# RPi_Extension_load.net
KiCad netlist of a schematic drawn in EAGLE
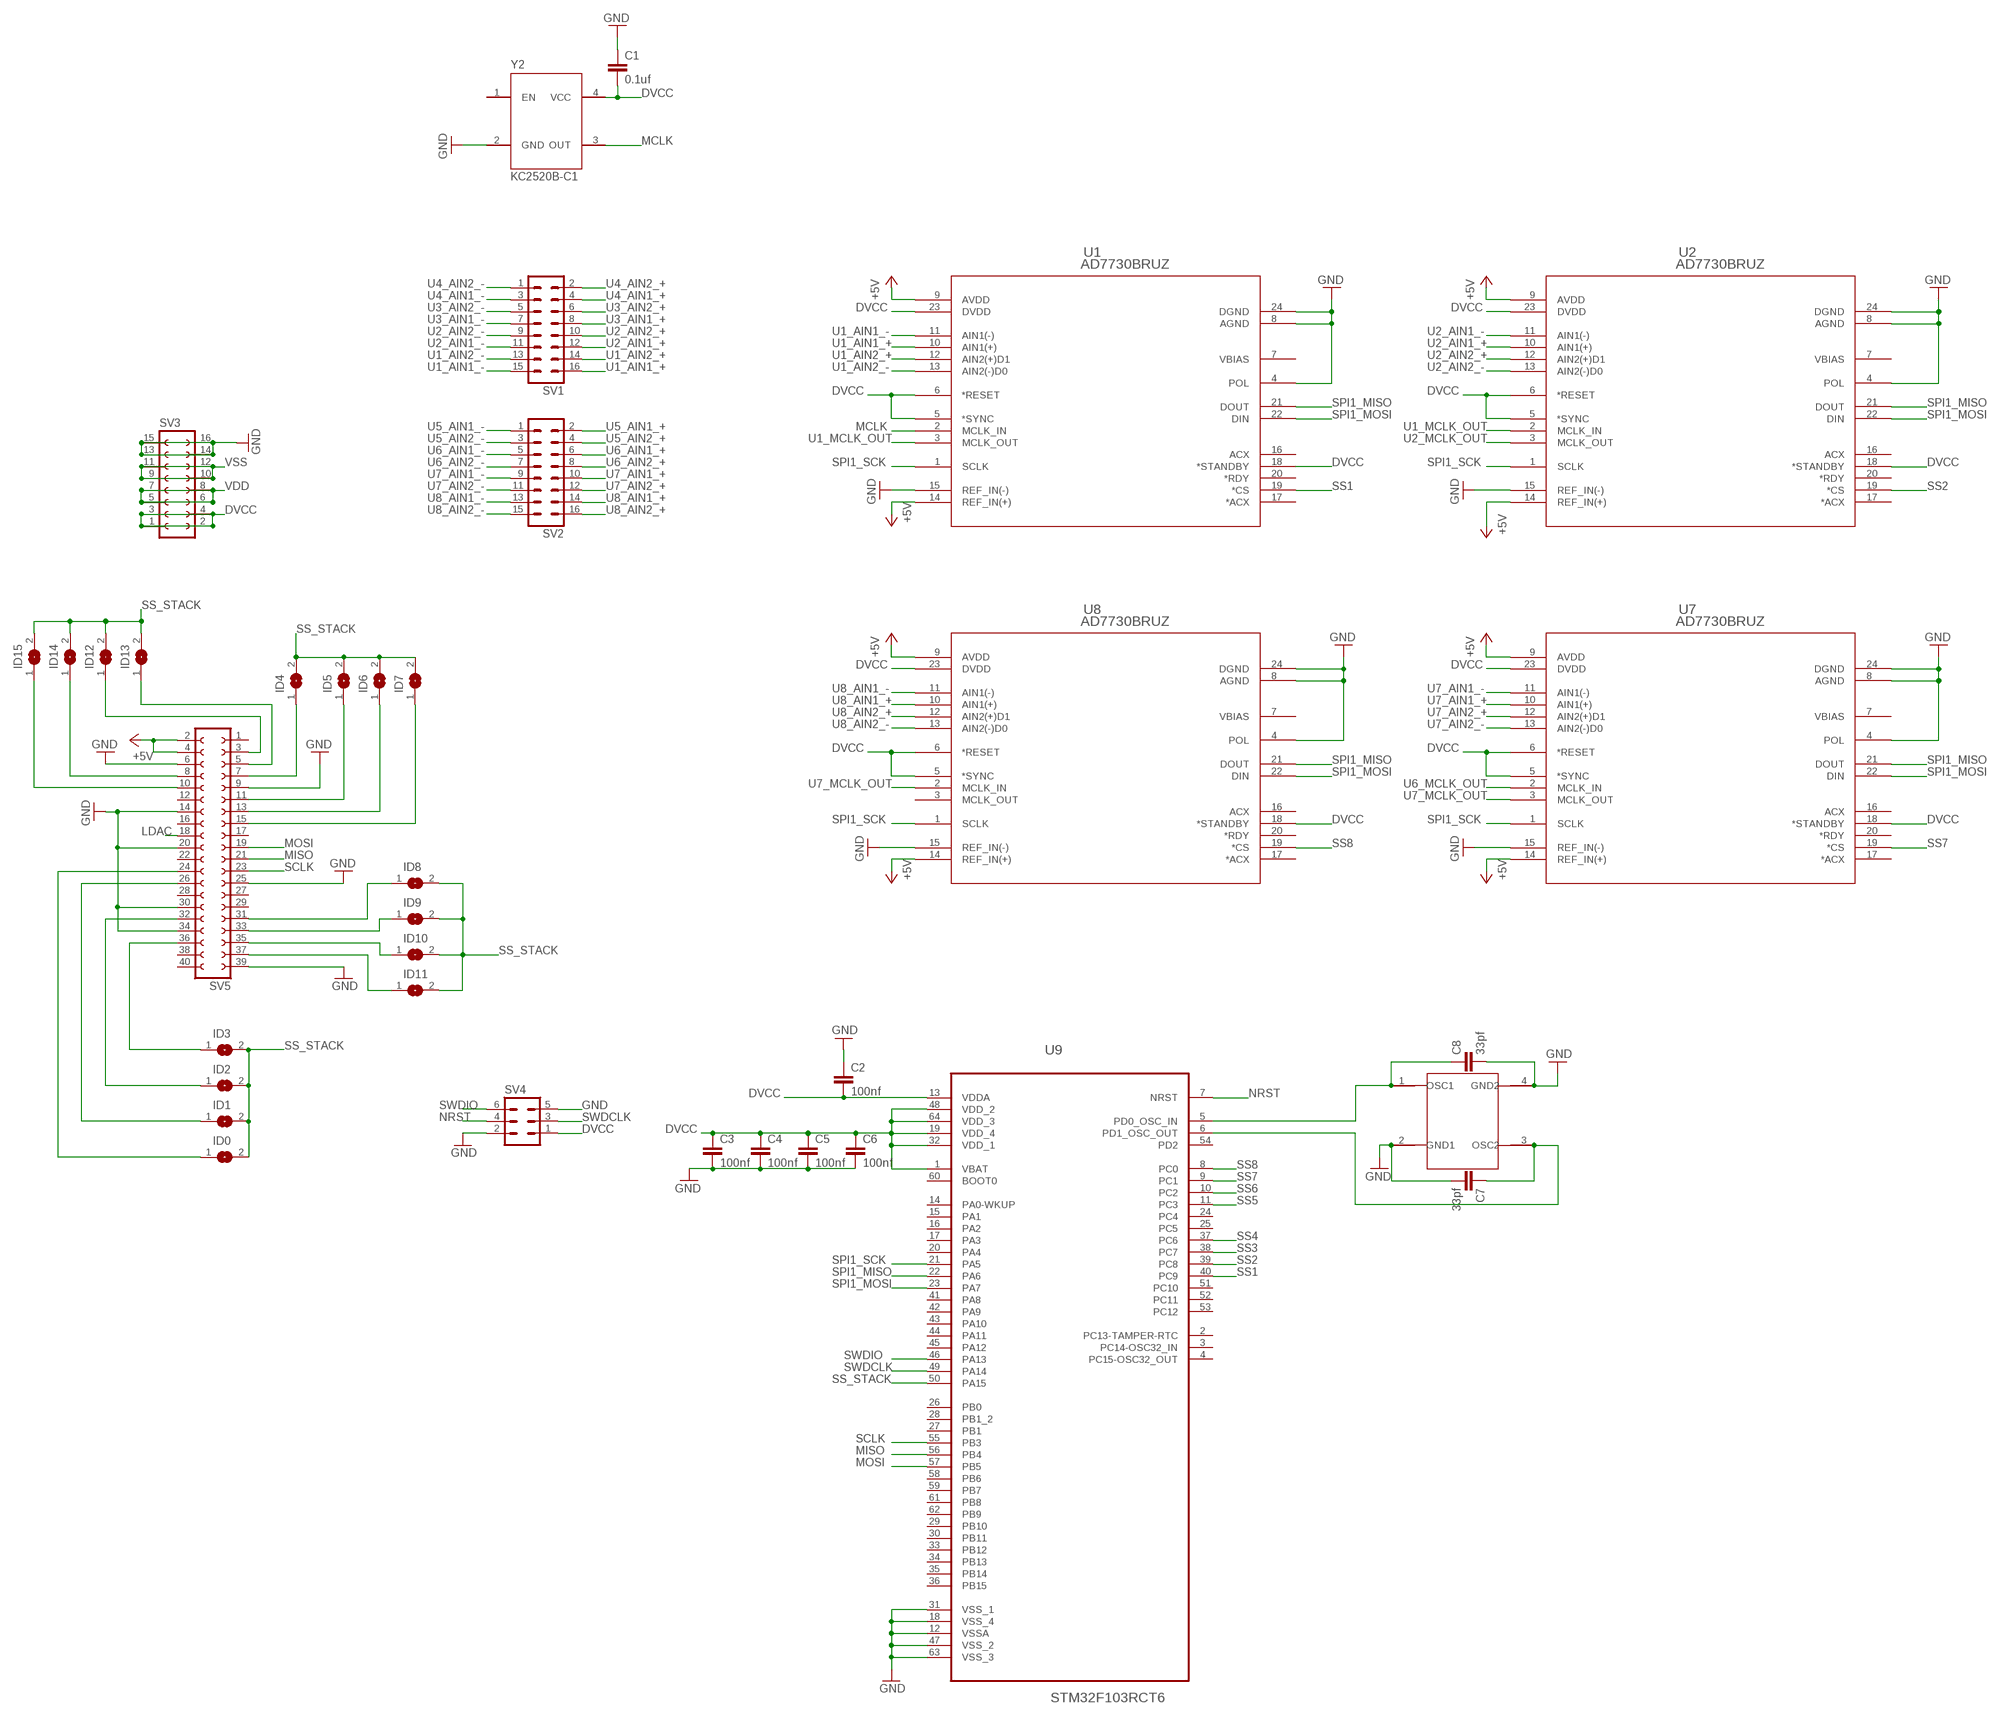
[diagram p0: schematic, sheet 1, part 1 of 2]
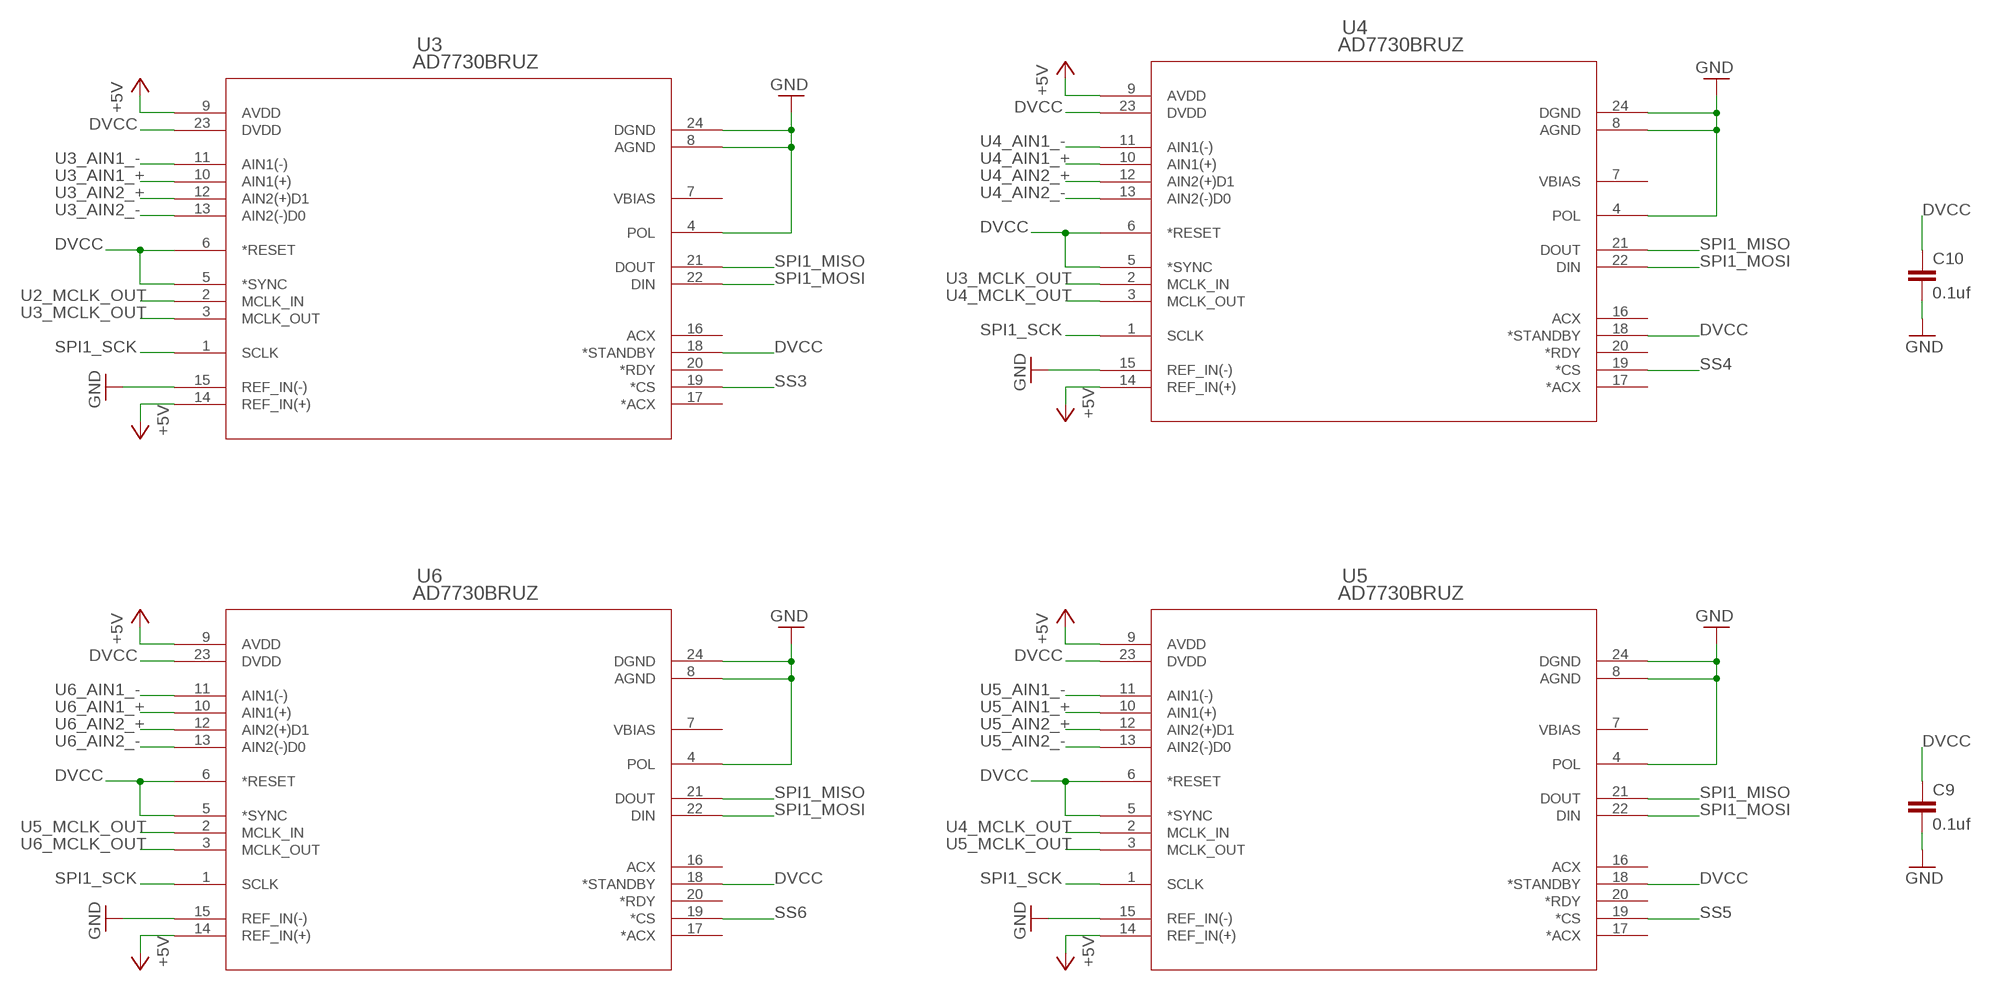
[diagram p1: schematic, sheet 1, part 2 of 2]

(export (version "E")
  (design (tool "Eeschema 10.0.6"))
  (components
    (comp (ref "C1")
      (value "0.1uf")
      (footprint "eagle-import:C0603")
      (libsource (lib "eagle-import") (part "C-EUC0603"))
    )
    (comp (ref "C2")
      (value "100nf")
      (footprint "eagle-import:C0603")
      (libsource (lib "eagle-import") (part "C-EUC0603"))
    )
    (comp (ref "C3")
      (value "100nf")
      (footprint "eagle-import:C0603")
      (libsource (lib "eagle-import") (part "C-EUC0603"))
    )
    (comp (ref "C4")
      (value "100nf")
      (footprint "eagle-import:C0603")
      (libsource (lib "eagle-import") (part "C-EUC0603"))
    )
    (comp (ref "C5")
      (value "100nf")
      (footprint "eagle-import:C0603")
      (libsource (lib "eagle-import") (part "C-EUC0603"))
    )
    (comp (ref "C6")
      (value "100nf")
      (footprint "eagle-import:C0603")
      (libsource (lib "eagle-import") (part "C-EUC0603"))
    )
    (comp (ref "C7")
      (value "33pf")
      (footprint "eagle-import:C0603")
      (libsource (lib "eagle-import") (part "C-EUC0603"))
    )
    (comp (ref "C8")
      (value "33pf")
      (footprint "eagle-import:C0603")
      (libsource (lib "eagle-import") (part "C-EUC0603"))
    )
    (comp (ref "C9")
      (value "0.1uf")
      (footprint "eagle-import:C0603")
      (libsource (lib "eagle-import") (part "C-EUC0603"))
    )
    (comp (ref "C10")
      (value "0.1uf")
      (footprint "eagle-import:C0603")
      (libsource (lib "eagle-import") (part "C-EUC0603"))
    )
    (comp (ref "ID0") (value "SJ") (footprint "eagle-import:SJ") (libsource (lib "eagle-import") (part "SJ")))
    (comp (ref "ID1") (value "SJ") (footprint "eagle-import:SJ") (libsource (lib "eagle-import") (part "SJ")))
    (comp (ref "ID2") (value "SJ") (footprint "eagle-import:SJ") (libsource (lib "eagle-import") (part "SJ")))
    (comp (ref "ID3") (value "SJ") (footprint "eagle-import:SJ") (libsource (lib "eagle-import") (part "SJ")))
    (comp (ref "ID4") (value "SJ") (footprint "eagle-import:SJ") (libsource (lib "eagle-import") (part "SJ")))
    (comp (ref "ID5") (value "SJ") (footprint "eagle-import:SJ") (libsource (lib "eagle-import") (part "SJ")))
    (comp (ref "ID6") (value "SJ") (footprint "eagle-import:SJ") (libsource (lib "eagle-import") (part "SJ")))
    (comp (ref "ID7") (value "SJ") (footprint "eagle-import:SJ") (libsource (lib "eagle-import") (part "SJ")))
    (comp (ref "ID8") (value "SJ") (footprint "eagle-import:SJ") (libsource (lib "eagle-import") (part "SJ")))
    (comp (ref "ID9") (value "SJ") (footprint "eagle-import:SJ") (libsource (lib "eagle-import") (part "SJ")))
    (comp (ref "ID10")
      (value "SJ")
      (footprint "eagle-import:SJ")
      (libsource (lib "eagle-import") (part "SJ"))
    )
    (comp (ref "ID11")
      (value "SJ")
      (footprint "eagle-import:SJ")
      (libsource (lib "eagle-import") (part "SJ"))
    )
    (comp (ref "ID12")
      (value "SJ")
      (footprint "eagle-import:SJ")
      (libsource (lib "eagle-import") (part "SJ"))
    )
    (comp (ref "ID13")
      (value "SJ")
      (footprint "eagle-import:SJ")
      (libsource (lib "eagle-import") (part "SJ"))
    )
    (comp (ref "ID14")
      (value "SJ")
      (footprint "eagle-import:SJ")
      (libsource (lib "eagle-import") (part "SJ"))
    )
    (comp (ref "ID15")
      (value "SJ")
      (footprint "eagle-import:SJ")
      (libsource (lib "eagle-import") (part "SJ"))
    )
    (comp (ref "SV1")
      (value "MA08-2W")
      (footprint "eagle-import:MA08-2W")
      (libsource (lib "eagle-import") (part "MA08-2W"))
    )
    (comp (ref "SV2")
      (value "MA08-2W")
      (footprint "eagle-import:MA08-2W")
      (libsource (lib "eagle-import") (part "MA08-2W"))
    )
    (comp (ref "SV3")
      (value "FE08-2")
      (footprint "eagle-import:FE08-2")
      (libsource (lib "eagle-import") (part "FE08-2"))
    )
    (comp (ref "SV4")
      (value "MA03-2")
      (footprint "eagle-import:MA03-2")
      (libsource (lib "eagle-import") (part "MA03-2"))
    )
    (comp (ref "SV5")
      (value "FE20-2")
      (footprint "eagle-import:FE20-2")
      (libsource (lib "eagle-import") (part "FE20-2"))
    )
    (comp (ref "U1")
      (value "AD7730BRUZ")
      (footprint "eagle-import:RU_24")
      (libsource (lib "eagle-import") (part "AD7730BRUZ"))
    )
    (comp (ref "U2")
      (value "AD7730BRUZ")
      (footprint "eagle-import:RU_24")
      (libsource (lib "eagle-import") (part "AD7730BRUZ"))
    )
    (comp (ref "U3")
      (value "AD7730BRUZ")
      (footprint "eagle-import:RU_24")
      (libsource (lib "eagle-import") (part "AD7730BRUZ"))
    )
    (comp (ref "U4")
      (value "AD7730BRUZ")
      (footprint "eagle-import:RU_24")
      (libsource (lib "eagle-import") (part "AD7730BRUZ"))
    )
    (comp (ref "U5")
      (value "AD7730BRUZ")
      (footprint "eagle-import:RU_24")
      (libsource (lib "eagle-import") (part "AD7730BRUZ"))
    )
    (comp (ref "U6")
      (value "AD7730BRUZ")
      (footprint "eagle-import:RU_24")
      (libsource (lib "eagle-import") (part "AD7730BRUZ"))
    )
    (comp (ref "U7")
      (value "AD7730BRUZ")
      (footprint "eagle-import:RU_24")
      (libsource (lib "eagle-import") (part "AD7730BRUZ"))
    )
    (comp (ref "U8")
      (value "AD7730BRUZ")
      (footprint "eagle-import:RU_24")
      (libsource (lib "eagle-import") (part "AD7730BRUZ"))
    )
    (comp (ref "U9")
      (value "STM32F103RCT6")
      (footprint "eagle-import:QFP50P1200X1200X160-64N")
      (libsource (lib "eagle-import") (part "STM32F103RCT6"))
    )
    (comp (ref "Y1")
      (value "ABM3B")
      (footprint "eagle-import:ABM3B")
      (libsource (lib "eagle-import") (part "ABM3B"))
    )
    (comp (ref "Y2")
      (value "KC2520B-C1")
      (footprint "eagle-import:KC2520B-C1")
      (libsource (lib "eagle-import") (part "KC2520B-C1"))
    )
  )
  (nets
    (net (code "1") (name "+5V") (class "Default")
      (node (ref "SV5") (pin "2") (pinfunction "2_2") (pintype "passive"))
      (node (ref "SV5") (pin "4") (pinfunction "4_4") (pintype "passive"))
      (node (ref "U1") (pin "14") (pinfunction "REF_IN(+)_14") (pintype "passive"))
      (node (ref "U1") (pin "9") (pinfunction "AVDD_9") (pintype "passive"))
      (node (ref "U2") (pin "14") (pinfunction "REF_IN(+)_14") (pintype "passive"))
      (node (ref "U2") (pin "9") (pinfunction "AVDD_9") (pintype "passive"))
      (node (ref "U3") (pin "14") (pinfunction "REF_IN(+)_14") (pintype "passive"))
      (node (ref "U3") (pin "9") (pinfunction "AVDD_9") (pintype "passive"))
      (node (ref "U4") (pin "14") (pinfunction "REF_IN(+)_14") (pintype "passive"))
      (node (ref "U4") (pin "9") (pinfunction "AVDD_9") (pintype "passive"))
      (node (ref "U5") (pin "14") (pinfunction "REF_IN(+)_14") (pintype "passive"))
      (node (ref "U5") (pin "9") (pinfunction "AVDD_9") (pintype "passive"))
      (node (ref "U6") (pin "14") (pinfunction "REF_IN(+)_14") (pintype "passive"))
      (node (ref "U6") (pin "9") (pinfunction "AVDD_9") (pintype "passive"))
      (node (ref "U7") (pin "14") (pinfunction "REF_IN(+)_14") (pintype "passive"))
      (node (ref "U7") (pin "9") (pinfunction "AVDD_9") (pintype "passive"))
      (node (ref "U8") (pin "14") (pinfunction "REF_IN(+)_14") (pintype "passive"))
      (node (ref "U8") (pin "9") (pinfunction "AVDD_9") (pintype "passive"))
    )
    (net (code "2") (name "/DVCC") (class "Default")
      (node (ref "C1") (pin "2") (pinfunction "2_2") (pintype "passive"))
      (node (ref "C10") (pin "1") (pinfunction "1_1") (pintype "passive"))
      (node (ref "C2") (pin "2") (pinfunction "2_2") (pintype "passive"))
      (node (ref "C3") (pin "1") (pinfunction "1_1") (pintype "passive"))
      (node (ref "C4") (pin "1") (pinfunction "1_1") (pintype "passive"))
      (node (ref "C5") (pin "1") (pinfunction "1_1") (pintype "passive"))
      (node (ref "C6") (pin "1") (pinfunction "1_1") (pintype "passive"))
      (node (ref "C9") (pin "1") (pinfunction "1_1") (pintype "passive"))
      (node (ref "SV3") (pin "1") (pinfunction "1_1") (pintype "passive"))
      (node (ref "SV3") (pin "2") (pinfunction "2_2") (pintype "passive"))
      (node (ref "SV3") (pin "3") (pinfunction "3_3") (pintype "passive"))
      (node (ref "SV3") (pin "4") (pinfunction "4_4") (pintype "passive"))
      (node (ref "SV4") (pin "1") (pinfunction "1_1") (pintype "passive"))
      (node (ref "U1") (pin "18") (pinfunction "*STANDBY_18") (pintype "passive"))
      (node (ref "U1") (pin "23") (pinfunction "DVDD_23") (pintype "passive"))
      (node (ref "U1") (pin "5") (pinfunction "*SYNC_5") (pintype "passive"))
      (node (ref "U1") (pin "6") (pinfunction "*RESET_6") (pintype "passive"))
      (node (ref "U2") (pin "18") (pinfunction "*STANDBY_18") (pintype "passive"))
      (node (ref "U2") (pin "23") (pinfunction "DVDD_23") (pintype "passive"))
      (node (ref "U2") (pin "5") (pinfunction "*SYNC_5") (pintype "passive"))
      (node (ref "U2") (pin "6") (pinfunction "*RESET_6") (pintype "passive"))
      (node (ref "U3") (pin "18") (pinfunction "*STANDBY_18") (pintype "passive"))
      (node (ref "U3") (pin "23") (pinfunction "DVDD_23") (pintype "passive"))
      (node (ref "U3") (pin "5") (pinfunction "*SYNC_5") (pintype "passive"))
      (node (ref "U3") (pin "6") (pinfunction "*RESET_6") (pintype "passive"))
      (node (ref "U4") (pin "18") (pinfunction "*STANDBY_18") (pintype "passive"))
      (node (ref "U4") (pin "23") (pinfunction "DVDD_23") (pintype "passive"))
      (node (ref "U4") (pin "5") (pinfunction "*SYNC_5") (pintype "passive"))
      (node (ref "U4") (pin "6") (pinfunction "*RESET_6") (pintype "passive"))
      (node (ref "U5") (pin "18") (pinfunction "*STANDBY_18") (pintype "passive"))
      (node (ref "U5") (pin "23") (pinfunction "DVDD_23") (pintype "passive"))
      (node (ref "U5") (pin "5") (pinfunction "*SYNC_5") (pintype "passive"))
      (node (ref "U5") (pin "6") (pinfunction "*RESET_6") (pintype "passive"))
      (node (ref "U6") (pin "18") (pinfunction "*STANDBY_18") (pintype "passive"))
      (node (ref "U6") (pin "23") (pinfunction "DVDD_23") (pintype "passive"))
      (node (ref "U6") (pin "5") (pinfunction "*SYNC_5") (pintype "passive"))
      (node (ref "U6") (pin "6") (pinfunction "*RESET_6") (pintype "passive"))
      (node (ref "U7") (pin "18") (pinfunction "*STANDBY_18") (pintype "passive"))
      (node (ref "U7") (pin "23") (pinfunction "DVDD_23") (pintype "passive"))
      (node (ref "U7") (pin "5") (pinfunction "*SYNC_5") (pintype "passive"))
      (node (ref "U7") (pin "6") (pinfunction "*RESET_6") (pintype "passive"))
      (node (ref "U8") (pin "18") (pinfunction "*STANDBY_18") (pintype "passive"))
      (node (ref "U8") (pin "23") (pinfunction "DVDD_23") (pintype "passive"))
      (node (ref "U8") (pin "5") (pinfunction "*SYNC_5") (pintype "passive"))
      (node (ref "U8") (pin "6") (pinfunction "*RESET_6") (pintype "passive"))
      (node (ref "U9") (pin "1") (pinfunction "VBAT_1") (pintype "input"))
      (node (ref "U9") (pin "13") (pinfunction "VDDA_13") (pintype "power_in"))
      (node (ref "U9") (pin "19") (pinfunction "VDD_4_19") (pintype "power_in"))
      (node (ref "U9") (pin "32") (pinfunction "VDD_1_32") (pintype "power_in"))
      (node (ref "U9") (pin "48") (pinfunction "VDD_2_48") (pintype "power_in"))
      (node (ref "U9") (pin "64") (pinfunction "VDD_3_64") (pintype "power_in"))
      (node (ref "Y2") (pin "4") (pinfunction "VCC_4") (pintype "bidirectional"))
    )
    (net (code "3") (name "/LDAC") (class "Default")
      (node (ref "SV5") (pin "18") (pinfunction "18_18") (pintype "passive"))
    )
    (net (code "4") (name "/MCLK") (class "Default")
      (node (ref "U1") (pin "2") (pinfunction "MCLK_IN_2") (pintype "passive"))
      (node (ref "Y2") (pin "3") (pinfunction "OUT_3") (pintype "bidirectional"))
    )
    (net (code "5") (name "/MISO") (class "Default")
      (node (ref "SV5") (pin "21") (pinfunction "21_21") (pintype "passive"))
      (node (ref "U9") (pin "56") (pinfunction "PB4_56") (pintype "bidirectional"))
    )
    (net (code "6") (name "/MOSI") (class "Default")
      (node (ref "SV5") (pin "19") (pinfunction "19_19") (pintype "passive"))
      (node (ref "U9") (pin "57") (pinfunction "PB5_57") (pintype "bidirectional"))
    )
    (net (code "7") (name "/NRST") (class "Default")
      (node (ref "SV4") (pin "4") (pinfunction "4_4") (pintype "passive"))
      (node (ref "U9") (pin "7") (pinfunction "NRST_7") (pintype "output"))
    )
    (net (code "8") (name "/PB7") (class "Default")
      (node (ref "U9") (pin "59") (pinfunction "PB7_59") (pintype "power_in"))
    )
    (net (code "9") (name "/SCLK") (class "Default")
      (node (ref "SV5") (pin "23") (pinfunction "23_23") (pintype "passive"))
      (node (ref "U9") (pin "55") (pinfunction "PB3_55") (pintype "bidirectional"))
    )
    (net (code "10") (name "/SPI1_MISO") (class "Default")
      (node (ref "U1") (pin "21") (pinfunction "DOUT_21") (pintype "passive"))
      (node (ref "U2") (pin "21") (pinfunction "DOUT_21") (pintype "passive"))
      (node (ref "U3") (pin "21") (pinfunction "DOUT_21") (pintype "passive"))
      (node (ref "U4") (pin "21") (pinfunction "DOUT_21") (pintype "passive"))
      (node (ref "U5") (pin "21") (pinfunction "DOUT_21") (pintype "passive"))
      (node (ref "U6") (pin "21") (pinfunction "DOUT_21") (pintype "passive"))
      (node (ref "U7") (pin "21") (pinfunction "DOUT_21") (pintype "passive"))
      (node (ref "U8") (pin "21") (pinfunction "DOUT_21") (pintype "passive"))
      (node (ref "U9") (pin "22") (pinfunction "PA6_22") (pintype "bidirectional"))
    )
    (net (code "11") (name "/SPI1_MOSI") (class "Default")
      (node (ref "U1") (pin "22") (pinfunction "DIN_22") (pintype "passive"))
      (node (ref "U2") (pin "22") (pinfunction "DIN_22") (pintype "passive"))
      (node (ref "U3") (pin "22") (pinfunction "DIN_22") (pintype "passive"))
      (node (ref "U4") (pin "22") (pinfunction "DIN_22") (pintype "passive"))
      (node (ref "U5") (pin "22") (pinfunction "DIN_22") (pintype "passive"))
      (node (ref "U6") (pin "22") (pinfunction "DIN_22") (pintype "passive"))
      (node (ref "U7") (pin "22") (pinfunction "DIN_22") (pintype "passive"))
      (node (ref "U8") (pin "22") (pinfunction "DIN_22") (pintype "passive"))
      (node (ref "U9") (pin "23") (pinfunction "PA7_23") (pintype "power_in"))
    )
    (net (code "12") (name "/SPI1_SCK") (class "Default")
      (node (ref "U1") (pin "1") (pinfunction "SCLK_1") (pintype "passive"))
      (node (ref "U2") (pin "1") (pinfunction "SCLK_1") (pintype "passive"))
      (node (ref "U3") (pin "1") (pinfunction "SCLK_1") (pintype "passive"))
      (node (ref "U4") (pin "1") (pinfunction "SCLK_1") (pintype "passive"))
      (node (ref "U5") (pin "1") (pinfunction "SCLK_1") (pintype "passive"))
      (node (ref "U6") (pin "1") (pinfunction "SCLK_1") (pintype "passive"))
      (node (ref "U7") (pin "1") (pinfunction "SCLK_1") (pintype "passive"))
      (node (ref "U8") (pin "1") (pinfunction "SCLK_1") (pintype "passive"))
      (node (ref "U9") (pin "21") (pinfunction "PA5_21") (pintype "bidirectional"))
    )
    (net (code "13") (name "/SS1") (class "Default")
      (node (ref "U1") (pin "19") (pinfunction "*CS_19") (pintype "passive"))
      (node (ref "U9") (pin "40") (pinfunction "PC9_40") (pintype "bidirectional"))
    )
    (net (code "14") (name "/SS2") (class "Default")
      (node (ref "U2") (pin "19") (pinfunction "*CS_19") (pintype "passive"))
      (node (ref "U9") (pin "39") (pinfunction "PC8_39") (pintype "bidirectional"))
    )
    (net (code "15") (name "/SS3") (class "Default")
      (node (ref "U3") (pin "19") (pinfunction "*CS_19") (pintype "passive"))
      (node (ref "U9") (pin "38") (pinfunction "PC7_38") (pintype "bidirectional"))
    )
    (net (code "16") (name "/SS4") (class "Default")
      (node (ref "U4") (pin "19") (pinfunction "*CS_19") (pintype "passive"))
      (node (ref "U9") (pin "37") (pinfunction "PC6_37") (pintype "bidirectional"))
    )
    (net (code "17") (name "/SS5") (class "Default")
      (node (ref "U5") (pin "19") (pinfunction "*CS_19") (pintype "passive"))
      (node (ref "U9") (pin "11") (pinfunction "PC3_11") (pintype "bidirectional"))
    )
    (net (code "18") (name "/SS6") (class "Default")
      (node (ref "U6") (pin "19") (pinfunction "*CS_19") (pintype "passive"))
      (node (ref "U9") (pin "10") (pinfunction "PC2_10") (pintype "bidirectional"))
    )
    (net (code "19") (name "/SS7") (class "Default")
      (node (ref "U7") (pin "19") (pinfunction "*CS_19") (pintype "passive"))
      (node (ref "U9") (pin "9") (pinfunction "PC1_9") (pintype "bidirectional"))
    )
    (net (code "20") (name "/SS8") (class "Default")
      (node (ref "U8") (pin "19") (pinfunction "*CS_19") (pintype "passive"))
      (node (ref "U9") (pin "8") (pinfunction "PC0_8") (pintype "bidirectional"))
    )
    (net (code "21") (name "/SS_STACK") (class "Default")
      (node (ref "ID0") (pin "2") (pinfunction "2_2") (pintype "passive"))
      (node (ref "ID1") (pin "2") (pinfunction "2_2") (pintype "passive"))
      (node (ref "ID10") (pin "2") (pinfunction "2_2") (pintype "passive"))
      (node (ref "ID11") (pin "2") (pinfunction "2_2") (pintype "passive"))
      (node (ref "ID12") (pin "2") (pinfunction "2_2") (pintype "passive"))
      (node (ref "ID13") (pin "2") (pinfunction "2_2") (pintype "passive"))
      (node (ref "ID14") (pin "2") (pinfunction "2_2") (pintype "passive"))
      (node (ref "ID15") (pin "2") (pinfunction "2_2") (pintype "passive"))
      (node (ref "ID2") (pin "2") (pinfunction "2_2") (pintype "passive"))
      (node (ref "ID3") (pin "2") (pinfunction "2_2") (pintype "passive"))
      (node (ref "ID4") (pin "2") (pinfunction "2_2") (pintype "passive"))
      (node (ref "ID5") (pin "2") (pinfunction "2_2") (pintype "passive"))
      (node (ref "ID6") (pin "2") (pinfunction "2_2") (pintype "passive"))
      (node (ref "ID7") (pin "2") (pinfunction "2_2") (pintype "passive"))
      (node (ref "ID8") (pin "2") (pinfunction "2_2") (pintype "passive"))
      (node (ref "ID9") (pin "2") (pinfunction "2_2") (pintype "passive"))
      (node (ref "U9") (pin "50") (pinfunction "PA15_50") (pintype "bidirectional"))
    )
    (net (code "22") (name "/SWDCLK") (class "Default")
      (node (ref "SV4") (pin "3") (pinfunction "3_3") (pintype "passive"))
      (node (ref "U9") (pin "49") (pinfunction "PA14_49") (pintype "bidirectional"))
    )
    (net (code "23") (name "/SWDIO") (class "Default")
      (node (ref "SV4") (pin "6") (pinfunction "6_6") (pintype "passive"))
      (node (ref "U9") (pin "46") (pinfunction "PA13_46") (pintype "bidirectional"))
    )
    (net (code "24") (name "/U1_AIN1_+") (class "Default")
      (node (ref "SV1") (pin "16") (pinfunction "16_16") (pintype "passive"))
      (node (ref "U1") (pin "10") (pinfunction "AIN1(+)_10") (pintype "passive"))
    )
    (net (code "25") (name "/U1_AIN1_-") (class "Default")
      (node (ref "SV1") (pin "15") (pinfunction "15_15") (pintype "passive"))
      (node (ref "U1") (pin "11") (pinfunction "AIN1(-)_11") (pintype "passive"))
    )
    (net (code "26") (name "/U1_AIN2_+") (class "Default")
      (node (ref "SV1") (pin "14") (pinfunction "14_14") (pintype "passive"))
      (node (ref "U1") (pin "12") (pinfunction "AIN2(+)D1_12") (pintype "passive"))
    )
    (net (code "27") (name "/U1_AIN2_-") (class "Default")
      (node (ref "SV1") (pin "13") (pinfunction "13_13") (pintype "passive"))
      (node (ref "U1") (pin "13") (pinfunction "AIN2(-)D0_13") (pintype "passive"))
    )
    (net (code "28") (name "/U1_MCLK_OUT") (class "Default")
      (node (ref "U1") (pin "3") (pinfunction "MCLK_OUT_3") (pintype "passive"))
      (node (ref "U2") (pin "2") (pinfunction "MCLK_IN_2") (pintype "passive"))
    )
    (net (code "29") (name "/U2_AIN1_+") (class "Default")
      (node (ref "SV1") (pin "12") (pinfunction "12_12") (pintype "passive"))
      (node (ref "U2") (pin "10") (pinfunction "AIN1(+)_10") (pintype "passive"))
    )
    (net (code "30") (name "/U2_AIN1_-") (class "Default")
      (node (ref "SV1") (pin "11") (pinfunction "11_11") (pintype "passive"))
      (node (ref "U2") (pin "11") (pinfunction "AIN1(-)_11") (pintype "passive"))
    )
    (net (code "31") (name "/U2_AIN2_+") (class "Default")
      (node (ref "SV1") (pin "10") (pinfunction "10_10") (pintype "passive"))
      (node (ref "U2") (pin "12") (pinfunction "AIN2(+)D1_12") (pintype "passive"))
    )
    (net (code "32") (name "/U2_AIN2_-") (class "Default")
      (node (ref "SV1") (pin "9") (pinfunction "9_9") (pintype "passive"))
      (node (ref "U2") (pin "13") (pinfunction "AIN2(-)D0_13") (pintype "passive"))
    )
    (net (code "33") (name "/U2_MCLK_OUT") (class "Default")
      (node (ref "U2") (pin "3") (pinfunction "MCLK_OUT_3") (pintype "passive"))
      (node (ref "U3") (pin "2") (pinfunction "MCLK_IN_2") (pintype "passive"))
    )
    (net (code "34") (name "/U3_AIN1_+") (class "Default")
      (node (ref "SV1") (pin "8") (pinfunction "8_8") (pintype "passive"))
      (node (ref "U3") (pin "10") (pinfunction "AIN1(+)_10") (pintype "passive"))
    )
    (net (code "35") (name "/U3_AIN1_-") (class "Default")
      (node (ref "SV1") (pin "7") (pinfunction "7_7") (pintype "passive"))
      (node (ref "U3") (pin "11") (pinfunction "AIN1(-)_11") (pintype "passive"))
    )
    (net (code "36") (name "/U3_AIN2_+") (class "Default")
      (node (ref "SV1") (pin "6") (pinfunction "6_6") (pintype "passive"))
      (node (ref "U3") (pin "12") (pinfunction "AIN2(+)D1_12") (pintype "passive"))
    )
    (net (code "37") (name "/U3_AIN2_-") (class "Default")
      (node (ref "SV1") (pin "5") (pinfunction "5_5") (pintype "passive"))
      (node (ref "U3") (pin "13") (pinfunction "AIN2(-)D0_13") (pintype "passive"))
    )
    (net (code "38") (name "/U3_MCLK_OUT") (class "Default")
      (node (ref "U3") (pin "3") (pinfunction "MCLK_OUT_3") (pintype "passive"))
      (node (ref "U4") (pin "2") (pinfunction "MCLK_IN_2") (pintype "passive"))
    )
    (net (code "39") (name "/U4_AIN1_+") (class "Default")
      (node (ref "SV1") (pin "4") (pinfunction "4_4") (pintype "passive"))
      (node (ref "U4") (pin "10") (pinfunction "AIN1(+)_10") (pintype "passive"))
    )
    (net (code "40") (name "/U4_AIN1_-") (class "Default")
      (node (ref "SV1") (pin "3") (pinfunction "3_3") (pintype "passive"))
      (node (ref "U4") (pin "11") (pinfunction "AIN1(-)_11") (pintype "passive"))
    )
    (net (code "41") (name "/U4_AIN2_+") (class "Default")
      (node (ref "SV1") (pin "2") (pinfunction "2_2") (pintype "passive"))
      (node (ref "U4") (pin "12") (pinfunction "AIN2(+)D1_12") (pintype "passive"))
    )
    (net (code "42") (name "/U4_AIN2_-") (class "Default")
      (node (ref "SV1") (pin "1") (pinfunction "1_1") (pintype "passive"))
      (node (ref "U4") (pin "13") (pinfunction "AIN2(-)D0_13") (pintype "passive"))
    )
    (net (code "43") (name "/U4_MCLK_OUT") (class "Default")
      (node (ref "U4") (pin "3") (pinfunction "MCLK_OUT_3") (pintype "passive"))
      (node (ref "U5") (pin "2") (pinfunction "MCLK_IN_2") (pintype "passive"))
    )
    (net (code "44") (name "/U5_AIN1_+") (class "Default")
      (node (ref "SV2") (pin "2") (pinfunction "2_2") (pintype "passive"))
      (node (ref "U5") (pin "10") (pinfunction "AIN1(+)_10") (pintype "passive"))
    )
    (net (code "45") (name "/U5_AIN1_-") (class "Default")
      (node (ref "SV2") (pin "1") (pinfunction "1_1") (pintype "passive"))
      (node (ref "U5") (pin "11") (pinfunction "AIN1(-)_11") (pintype "passive"))
    )
    (net (code "46") (name "/U5_AIN2_+") (class "Default")
      (node (ref "SV2") (pin "4") (pinfunction "4_4") (pintype "passive"))
      (node (ref "U5") (pin "12") (pinfunction "AIN2(+)D1_12") (pintype "passive"))
    )
    (net (code "47") (name "/U5_AIN2_-") (class "Default")
      (node (ref "SV2") (pin "3") (pinfunction "3_3") (pintype "passive"))
      (node (ref "U5") (pin "13") (pinfunction "AIN2(-)D0_13") (pintype "passive"))
    )
    (net (code "48") (name "/U5_MCLK_OUT") (class "Default")
      (node (ref "U5") (pin "3") (pinfunction "MCLK_OUT_3") (pintype "passive"))
      (node (ref "U6") (pin "2") (pinfunction "MCLK_IN_2") (pintype "passive"))
    )
    (net (code "49") (name "/U6_AIN1_+") (class "Default")
      (node (ref "SV2") (pin "6") (pinfunction "6_6") (pintype "passive"))
      (node (ref "U6") (pin "10") (pinfunction "AIN1(+)_10") (pintype "passive"))
    )
    (net (code "50") (name "/U6_AIN1_-") (class "Default")
      (node (ref "SV2") (pin "5") (pinfunction "5_5") (pintype "passive"))
      (node (ref "U6") (pin "11") (pinfunction "AIN1(-)_11") (pintype "passive"))
    )
    (net (code "51") (name "/U6_AIN2_+") (class "Default")
      (node (ref "SV2") (pin "8") (pinfunction "8_8") (pintype "passive"))
      (node (ref "U6") (pin "12") (pinfunction "AIN2(+)D1_12") (pintype "passive"))
    )
    (net (code "52") (name "/U6_AIN2_-") (class "Default")
      (node (ref "SV2") (pin "7") (pinfunction "7_7") (pintype "passive"))
      (node (ref "U6") (pin "13") (pinfunction "AIN2(-)D0_13") (pintype "passive"))
    )
    (net (code "53") (name "/U6_MCLK_OUT") (class "Default")
      (node (ref "U6") (pin "3") (pinfunction "MCLK_OUT_3") (pintype "passive"))
      (node (ref "U7") (pin "2") (pinfunction "MCLK_IN_2") (pintype "passive"))
    )
    (net (code "54") (name "/U7_AIN1_+") (class "Default")
      (node (ref "SV2") (pin "10") (pinfunction "10_10") (pintype "passive"))
      (node (ref "U7") (pin "10") (pinfunction "AIN1(+)_10") (pintype "passive"))
    )
    (net (code "55") (name "/U7_AIN1_-") (class "Default")
      (node (ref "SV2") (pin "9") (pinfunction "9_9") (pintype "passive"))
      (node (ref "U7") (pin "11") (pinfunction "AIN1(-)_11") (pintype "passive"))
    )
    (net (code "56") (name "/U7_AIN2_+") (class "Default")
      (node (ref "SV2") (pin "12") (pinfunction "12_12") (pintype "passive"))
      (node (ref "U7") (pin "12") (pinfunction "AIN2(+)D1_12") (pintype "passive"))
    )
    (net (code "57") (name "/U7_AIN2_-") (class "Default")
      (node (ref "SV2") (pin "11") (pinfunction "11_11") (pintype "passive"))
      (node (ref "U7") (pin "13") (pinfunction "AIN2(-)D0_13") (pintype "passive"))
    )
    (net (code "58") (name "/U7_MCLK_OUT") (class "Default")
      (node (ref "U7") (pin "3") (pinfunction "MCLK_OUT_3") (pintype "passive"))
      (node (ref "U8") (pin "2") (pinfunction "MCLK_IN_2") (pintype "passive"))
    )
    (net (code "59") (name "/U8_AIN1_+") (class "Default")
      (node (ref "SV2") (pin "14") (pinfunction "14_14") (pintype "passive"))
      (node (ref "U8") (pin "10") (pinfunction "AIN1(+)_10") (pintype "passive"))
    )
    (net (code "60") (name "/U8_AIN1_-") (class "Default")
      (node (ref "SV2") (pin "13") (pinfunction "13_13") (pintype "passive"))
      (node (ref "U8") (pin "11") (pinfunction "AIN1(-)_11") (pintype "passive"))
    )
    (net (code "61") (name "/U8_AIN2_+") (class "Default")
      (node (ref "SV2") (pin "16") (pinfunction "16_16") (pintype "passive"))
      (node (ref "U8") (pin "12") (pinfunction "AIN2(+)D1_12") (pintype "passive"))
    )
    (net (code "62") (name "/U8_AIN2_-") (class "Default")
      (node (ref "SV2") (pin "15") (pinfunction "15_15") (pintype "passive"))
      (node (ref "U8") (pin "13") (pinfunction "AIN2(-)D0_13") (pintype "passive"))
    )
    (net (code "63") (name "/VDD") (class "Default")
      (node (ref "SV3") (pin "5") (pinfunction "5_5") (pintype "passive"))
      (node (ref "SV3") (pin "6") (pinfunction "6_6") (pintype "passive"))
      (node (ref "SV3") (pin "7") (pinfunction "7_7") (pintype "passive"))
      (node (ref "SV3") (pin "8") (pinfunction "8_8") (pintype "passive"))
    )
    (net (code "64") (name "/VSS") (class "Default")
      (node (ref "SV3") (pin "10") (pinfunction "10_10") (pintype "passive"))
      (node (ref "SV3") (pin "11") (pinfunction "11_11") (pintype "passive"))
      (node (ref "SV3") (pin "12") (pinfunction "12_12") (pintype "passive"))
      (node (ref "SV3") (pin "9") (pinfunction "9_9") (pintype "passive"))
    )
    (net (code "65") (name "GND") (class "Default")
      (node (ref "C1") (pin "1") (pinfunction "1_1") (pintype "passive"))
      (node (ref "C10") (pin "2") (pinfunction "2_2") (pintype "passive"))
      (node (ref "C2") (pin "1") (pinfunction "1_1") (pintype "passive"))
      (node (ref "C3") (pin "2") (pinfunction "2_2") (pintype "passive"))
      (node (ref "C4") (pin "2") (pinfunction "2_2") (pintype "passive"))
      (node (ref "C5") (pin "2") (pinfunction "2_2") (pintype "passive"))
      (node (ref "C6") (pin "2") (pinfunction "2_2") (pintype "passive"))
      (node (ref "C7") (pin "2") (pinfunction "2_2") (pintype "passive"))
      (node (ref "C8") (pin "2") (pinfunction "2_2") (pintype "passive"))
      (node (ref "C9") (pin "2") (pinfunction "2_2") (pintype "passive"))
      (node (ref "SV3") (pin "13") (pinfunction "13_13") (pintype "passive"))
      (node (ref "SV3") (pin "14") (pinfunction "14_14") (pintype "passive"))
      (node (ref "SV3") (pin "15") (pinfunction "15_15") (pintype "passive"))
      (node (ref "SV3") (pin "16") (pinfunction "16_16") (pintype "passive"))
      (node (ref "SV4") (pin "2") (pinfunction "2_2") (pintype "passive"))
      (node (ref "SV4") (pin "5") (pinfunction "5_5") (pintype "passive"))
      (node (ref "SV5") (pin "14") (pinfunction "14_14") (pintype "passive"))
      (node (ref "SV5") (pin "20") (pinfunction "20_20") (pintype "passive"))
      (node (ref "SV5") (pin "25") (pinfunction "25_25") (pintype "passive"))
      (node (ref "SV5") (pin "30") (pinfunction "30_30") (pintype "passive"))
      (node (ref "SV5") (pin "34") (pinfunction "34_34") (pintype "passive"))
      (node (ref "SV5") (pin "39") (pinfunction "39_39") (pintype "passive"))
      (node (ref "SV5") (pin "6") (pinfunction "6_6") (pintype "passive"))
      (node (ref "SV5") (pin "9") (pinfunction "9_9") (pintype "passive"))
      (node (ref "U1") (pin "15") (pinfunction "REF_IN(-)_15") (pintype "passive"))
      (node (ref "U1") (pin "24") (pinfunction "DGND_24") (pintype "passive"))
      (node (ref "U1") (pin "4") (pinfunction "POL_4") (pintype "passive"))
      (node (ref "U1") (pin "8") (pinfunction "AGND_8") (pintype "passive"))
      (node (ref "U2") (pin "15") (pinfunction "REF_IN(-)_15") (pintype "passive"))
      (node (ref "U2") (pin "24") (pinfunction "DGND_24") (pintype "passive"))
      (node (ref "U2") (pin "4") (pinfunction "POL_4") (pintype "passive"))
      (node (ref "U2") (pin "8") (pinfunction "AGND_8") (pintype "passive"))
      (node (ref "U3") (pin "15") (pinfunction "REF_IN(-)_15") (pintype "passive"))
      (node (ref "U3") (pin "24") (pinfunction "DGND_24") (pintype "passive"))
      (node (ref "U3") (pin "4") (pinfunction "POL_4") (pintype "passive"))
      (node (ref "U3") (pin "8") (pinfunction "AGND_8") (pintype "passive"))
      (node (ref "U4") (pin "15") (pinfunction "REF_IN(-)_15") (pintype "passive"))
      (node (ref "U4") (pin "24") (pinfunction "DGND_24") (pintype "passive"))
      (node (ref "U4") (pin "4") (pinfunction "POL_4") (pintype "passive"))
      (node (ref "U4") (pin "8") (pinfunction "AGND_8") (pintype "passive"))
      (node (ref "U5") (pin "15") (pinfunction "REF_IN(-)_15") (pintype "passive"))
      (node (ref "U5") (pin "24") (pinfunction "DGND_24") (pintype "passive"))
      (node (ref "U5") (pin "4") (pinfunction "POL_4") (pintype "passive"))
      (node (ref "U5") (pin "8") (pinfunction "AGND_8") (pintype "passive"))
      (node (ref "U6") (pin "15") (pinfunction "REF_IN(-)_15") (pintype "passive"))
      (node (ref "U6") (pin "24") (pinfunction "DGND_24") (pintype "passive"))
      (node (ref "U6") (pin "4") (pinfunction "POL_4") (pintype "passive"))
      (node (ref "U6") (pin "8") (pinfunction "AGND_8") (pintype "passive"))
      (node (ref "U7") (pin "15") (pinfunction "REF_IN(-)_15") (pintype "passive"))
      (node (ref "U7") (pin "24") (pinfunction "DGND_24") (pintype "passive"))
      (node (ref "U7") (pin "4") (pinfunction "POL_4") (pintype "passive"))
      (node (ref "U7") (pin "8") (pinfunction "AGND_8") (pintype "passive"))
      (node (ref "U8") (pin "15") (pinfunction "REF_IN(-)_15") (pintype "passive"))
      (node (ref "U8") (pin "24") (pinfunction "DGND_24") (pintype "passive"))
      (node (ref "U8") (pin "4") (pinfunction "POL_4") (pintype "passive"))
      (node (ref "U8") (pin "8") (pinfunction "AGND_8") (pintype "passive"))
      (node (ref "U9") (pin "12") (pinfunction "VSSA_12") (pintype "passive"))
      (node (ref "U9") (pin "18") (pinfunction "VSS_4_18") (pintype "passive"))
      (node (ref "U9") (pin "31") (pinfunction "VSS_1_31") (pintype "passive"))
      (node (ref "U9") (pin "47") (pinfunction "VSS_2_47") (pintype "passive"))
      (node (ref "U9") (pin "63") (pinfunction "VSS_3_63") (pintype "passive"))
      (node (ref "Y1") (pin "2") (pinfunction "GND1_2") (pintype "bidirectional"))
      (node (ref "Y1") (pin "4") (pinfunction "GND2_4") (pintype "bidirectional"))
      (node (ref "Y2") (pin "2") (pinfunction "GND_2") (pintype "bidirectional"))
    )
    (net (code "66") (name "Net-(ID0-Pad1)") (class "Default")
      (node (ref "ID0") (pin "1") (pinfunction "1_1") (pintype "passive"))
      (node (ref "SV5") (pin "24") (pinfunction "24_24") (pintype "passive"))
    )
    (net (code "67") (name "Net-(ID1-Pad1)") (class "Default")
      (node (ref "ID1") (pin "1") (pinfunction "1_1") (pintype "passive"))
      (node (ref "SV5") (pin "26") (pinfunction "26_26") (pintype "passive"))
    )
    (net (code "68") (name "Net-(ID2-Pad1)") (class "Default")
      (node (ref "ID2") (pin "1") (pinfunction "1_1") (pintype "passive"))
      (node (ref "SV5") (pin "32") (pinfunction "32_32") (pintype "passive"))
    )
    (net (code "69") (name "Net-(ID3-Pad1)") (class "Default")
      (node (ref "ID3") (pin "1") (pinfunction "1_1") (pintype "passive"))
      (node (ref "SV5") (pin "36") (pinfunction "36_36") (pintype "passive"))
    )
    (net (code "70") (name "Net-(ID4-Pad1)") (class "Default")
      (node (ref "ID4") (pin "1") (pinfunction "1_1") (pintype "passive"))
      (node (ref "SV5") (pin "7") (pinfunction "7_7") (pintype "passive"))
    )
    (net (code "71") (name "Net-(ID5-Pad1)") (class "Default")
      (node (ref "ID5") (pin "1") (pinfunction "1_1") (pintype "passive"))
      (node (ref "SV5") (pin "11") (pinfunction "11_11") (pintype "passive"))
    )
    (net (code "72") (name "Net-(ID6-Pad1)") (class "Default")
      (node (ref "ID6") (pin "1") (pinfunction "1_1") (pintype "passive"))
      (node (ref "SV5") (pin "13") (pinfunction "13_13") (pintype "passive"))
    )
    (net (code "73") (name "Net-(ID7-Pad1)") (class "Default")
      (node (ref "ID7") (pin "1") (pinfunction "1_1") (pintype "passive"))
      (node (ref "SV5") (pin "15") (pinfunction "15_15") (pintype "passive"))
    )
    (net (code "74") (name "Net-(ID8-Pad1)") (class "Default")
      (node (ref "ID8") (pin "1") (pinfunction "1_1") (pintype "passive"))
      (node (ref "SV5") (pin "31") (pinfunction "31_31") (pintype "passive"))
    )
    (net (code "75") (name "Net-(ID9-Pad1)") (class "Default")
      (node (ref "ID9") (pin "1") (pinfunction "1_1") (pintype "passive"))
      (node (ref "SV5") (pin "33") (pinfunction "33_33") (pintype "passive"))
    )
    (net (code "76") (name "Net-(ID10-Pad1)") (class "Default")
      (node (ref "ID10") (pin "1") (pinfunction "1_1") (pintype "passive"))
      (node (ref "SV5") (pin "35") (pinfunction "35_35") (pintype "passive"))
    )
    (net (code "77") (name "Net-(ID11-Pad1)") (class "Default")
      (node (ref "ID11") (pin "1") (pinfunction "1_1") (pintype "passive"))
      (node (ref "SV5") (pin "37") (pinfunction "37_37") (pintype "passive"))
    )
    (net (code "78") (name "Net-(ID12-Pad1)") (class "Default")
      (node (ref "ID12") (pin "1") (pinfunction "1_1") (pintype "passive"))
      (node (ref "SV5") (pin "3") (pinfunction "3_3") (pintype "passive"))
    )
    (net (code "79") (name "Net-(ID13-Pad1)") (class "Default")
      (node (ref "ID13") (pin "1") (pinfunction "1_1") (pintype "passive"))
      (node (ref "SV5") (pin "5") (pinfunction "5_5") (pintype "passive"))
    )
    (net (code "80") (name "Net-(ID14-Pad1)") (class "Default")
      (node (ref "ID14") (pin "1") (pinfunction "1_1") (pintype "passive"))
      (node (ref "SV5") (pin "8") (pinfunction "8_8") (pintype "passive"))
    )
    (net (code "81") (name "Net-(ID15-Pad1)") (class "Default")
      (node (ref "ID15") (pin "1") (pinfunction "1_1") (pintype "passive"))
      (node (ref "SV5") (pin "10") (pinfunction "10_10") (pintype "passive"))
    )
    (net (code "82") (name "Net-(U9-PD0_OSC_IN)") (class "Default")
      (node (ref "C8") (pin "1") (pinfunction "1_1") (pintype "passive"))
      (node (ref "U9") (pin "5") (pinfunction "PD0_OSC_IN_5") (pintype "input"))
      (node (ref "Y1") (pin "1") (pinfunction "OSC1_1") (pintype "bidirectional"))
    )
    (net (code "83") (name "Net-(U9-PD1_OSC_OUT)") (class "Default")
      (node (ref "C7") (pin "1") (pinfunction "1_1") (pintype "passive"))
      (node (ref "U9") (pin "6") (pinfunction "PD1_OSC_OUT_6") (pintype "output"))
      (node (ref "Y1") (pin "3") (pinfunction "OSC2_3") (pintype "bidirectional"))
    )
    (net (code "84") (name "unconnected-(SV5-Pad1)") (class "Default")
      (node (ref "SV5") (pin "1") (pinfunction "1_1") (pintype "passive"))
    )
    (net (code "85") (name "unconnected-(SV5-Pad12)") (class "Default")
      (node (ref "SV5") (pin "12") (pinfunction "12_12") (pintype "passive"))
    )
    (net (code "86") (name "unconnected-(SV5-Pad16)") (class "Default")
      (node (ref "SV5") (pin "16") (pinfunction "16_16") (pintype "passive"))
    )
    (net (code "87") (name "unconnected-(SV5-Pad17)") (class "Default")
      (node (ref "SV5") (pin "17") (pinfunction "17_17") (pintype "passive"))
    )
    (net (code "88") (name "unconnected-(SV5-Pad22)") (class "Default")
      (node (ref "SV5") (pin "22") (pinfunction "22_22") (pintype "passive"))
    )
    (net (code "89") (name "unconnected-(SV5-Pad27)") (class "Default")
      (node (ref "SV5") (pin "27") (pinfunction "27_27") (pintype "passive"))
    )
    (net (code "90") (name "unconnected-(SV5-Pad28)") (class "Default")
      (node (ref "SV5") (pin "28") (pinfunction "28_28") (pintype "passive"))
    )
    (net (code "91") (name "unconnected-(SV5-Pad29)") (class "Default")
      (node (ref "SV5") (pin "29") (pinfunction "29_29") (pintype "passive"))
    )
    (net (code "92") (name "unconnected-(SV5-Pad38)") (class "Default")
      (node (ref "SV5") (pin "38") (pinfunction "38_38") (pintype "passive"))
    )
    (net (code "93") (name "unconnected-(SV5-Pad40)") (class "Default")
      (node (ref "SV5") (pin "40") (pinfunction "40_40") (pintype "passive"))
    )
    (net (code "94") (name "unconnected-(U1-*ACX-Pad17)") (class "Default")
      (node (ref "U1") (pin "17") (pinfunction "*ACX_17") (pintype "passive"))
    )
    (net (code "95") (name "unconnected-(U1-*RDY-Pad20)") (class "Default")
      (node (ref "U1") (pin "20") (pinfunction "*RDY_20") (pintype "passive"))
    )
    (net (code "96") (name "unconnected-(U1-ACX-Pad16)") (class "Default")
      (node (ref "U1") (pin "16") (pinfunction "ACX_16") (pintype "passive"))
    )
    (net (code "97") (name "unconnected-(U1-VBIAS-Pad7)") (class "Default")
      (node (ref "U1") (pin "7") (pinfunction "VBIAS_7") (pintype "passive"))
    )
    (net (code "98") (name "unconnected-(U2-*ACX-Pad17)") (class "Default")
      (node (ref "U2") (pin "17") (pinfunction "*ACX_17") (pintype "passive"))
    )
    (net (code "99") (name "unconnected-(U2-*RDY-Pad20)") (class "Default")
      (node (ref "U2") (pin "20") (pinfunction "*RDY_20") (pintype "passive"))
    )
    (net (code "100") (name "unconnected-(U2-ACX-Pad16)") (class "Default")
      (node (ref "U2") (pin "16") (pinfunction "ACX_16") (pintype "passive"))
    )
    (net (code "101") (name "unconnected-(U2-VBIAS-Pad7)") (class "Default")
      (node (ref "U2") (pin "7") (pinfunction "VBIAS_7") (pintype "passive"))
    )
    (net (code "102") (name "unconnected-(U3-*ACX-Pad17)") (class "Default")
      (node (ref "U3") (pin "17") (pinfunction "*ACX_17") (pintype "passive"))
    )
    (net (code "103") (name "unconnected-(U3-*RDY-Pad20)") (class "Default")
      (node (ref "U3") (pin "20") (pinfunction "*RDY_20") (pintype "passive"))
    )
    (net (code "104") (name "unconnected-(U3-ACX-Pad16)") (class "Default")
      (node (ref "U3") (pin "16") (pinfunction "ACX_16") (pintype "passive"))
    )
    (net (code "105") (name "unconnected-(U3-VBIAS-Pad7)") (class "Default")
      (node (ref "U3") (pin "7") (pinfunction "VBIAS_7") (pintype "passive"))
    )
    (net (code "106") (name "unconnected-(U4-*ACX-Pad17)") (class "Default")
      (node (ref "U4") (pin "17") (pinfunction "*ACX_17") (pintype "passive"))
    )
    (net (code "107") (name "unconnected-(U4-*RDY-Pad20)") (class "Default")
      (node (ref "U4") (pin "20") (pinfunction "*RDY_20") (pintype "passive"))
    )
    (net (code "108") (name "unconnected-(U4-ACX-Pad16)") (class "Default")
      (node (ref "U4") (pin "16") (pinfunction "ACX_16") (pintype "passive"))
    )
    (net (code "109") (name "unconnected-(U4-VBIAS-Pad7)") (class "Default")
      (node (ref "U4") (pin "7") (pinfunction "VBIAS_7") (pintype "passive"))
    )
    (net (code "110") (name "unconnected-(U5-*ACX-Pad17)") (class "Default")
      (node (ref "U5") (pin "17") (pinfunction "*ACX_17") (pintype "passive"))
    )
    (net (code "111") (name "unconnected-(U5-*RDY-Pad20)") (class "Default")
      (node (ref "U5") (pin "20") (pinfunction "*RDY_20") (pintype "passive"))
    )
    (net (code "112") (name "unconnected-(U5-ACX-Pad16)") (class "Default")
      (node (ref "U5") (pin "16") (pinfunction "ACX_16") (pintype "passive"))
    )
    (net (code "113") (name "unconnected-(U5-VBIAS-Pad7)") (class "Default")
      (node (ref "U5") (pin "7") (pinfunction "VBIAS_7") (pintype "passive"))
    )
    (net (code "114") (name "unconnected-(U6-*ACX-Pad17)") (class "Default")
      (node (ref "U6") (pin "17") (pinfunction "*ACX_17") (pintype "passive"))
    )
    (net (code "115") (name "unconnected-(U6-*RDY-Pad20)") (class "Default")
      (node (ref "U6") (pin "20") (pinfunction "*RDY_20") (pintype "passive"))
    )
    (net (code "116") (name "unconnected-(U6-ACX-Pad16)") (class "Default")
      (node (ref "U6") (pin "16") (pinfunction "ACX_16") (pintype "passive"))
    )
    (net (code "117") (name "unconnected-(U6-VBIAS-Pad7)") (class "Default")
      (node (ref "U6") (pin "7") (pinfunction "VBIAS_7") (pintype "passive"))
    )
    (net (code "118") (name "unconnected-(U7-*ACX-Pad17)") (class "Default")
      (node (ref "U7") (pin "17") (pinfunction "*ACX_17") (pintype "passive"))
    )
    (net (code "119") (name "unconnected-(U7-*RDY-Pad20)") (class "Default")
      (node (ref "U7") (pin "20") (pinfunction "*RDY_20") (pintype "passive"))
    )
    (net (code "120") (name "unconnected-(U7-ACX-Pad16)") (class "Default")
      (node (ref "U7") (pin "16") (pinfunction "ACX_16") (pintype "passive"))
    )
    (net (code "121") (name "unconnected-(U7-VBIAS-Pad7)") (class "Default")
      (node (ref "U7") (pin "7") (pinfunction "VBIAS_7") (pintype "passive"))
    )
    (net (code "122") (name "unconnected-(U8-*ACX-Pad17)") (class "Default")
      (node (ref "U8") (pin "17") (pinfunction "*ACX_17") (pintype "passive"))
    )
    (net (code "123") (name "unconnected-(U8-*RDY-Pad20)") (class "Default")
      (node (ref "U8") (pin "20") (pinfunction "*RDY_20") (pintype "passive"))
    )
    (net (code "124") (name "unconnected-(U8-ACX-Pad16)") (class "Default")
      (node (ref "U8") (pin "16") (pinfunction "ACX_16") (pintype "passive"))
    )
    (net (code "125") (name "unconnected-(U8-MCLK_OUT-Pad3)") (class "Default")
      (node (ref "U8") (pin "3") (pinfunction "MCLK_OUT_3") (pintype "passive"))
    )
    (net (code "126") (name "unconnected-(U8-VBIAS-Pad7)") (class "Default")
      (node (ref "U8") (pin "7") (pinfunction "VBIAS_7") (pintype "passive"))
    )
    (net (code "127") (name "unconnected-(U9-BOOT0-Pad60)") (class "Default")
      (node (ref "U9") (pin "60") (pinfunction "BOOT0_60") (pintype "passive"))
    )
    (net (code "128") (name "unconnected-(U9-PA0-WKUP-Pad14)") (class "Default")
      (node (ref "U9") (pin "14") (pinfunction "PA0-WKUP_14") (pintype "bidirectional"))
    )
    (net (code "129") (name "unconnected-(U9-PA1-Pad15)") (class "Default")
      (node (ref "U9") (pin "15") (pinfunction "PA1_15") (pintype "bidirectional"))
    )
    (net (code "130") (name "unconnected-(U9-PA2-Pad16)") (class "Default")
      (node (ref "U9") (pin "16") (pinfunction "PA2_16") (pintype "bidirectional"))
    )
    (net (code "131") (name "unconnected-(U9-PA3-Pad17)") (class "Default")
      (node (ref "U9") (pin "17") (pinfunction "PA3_17") (pintype "bidirectional"))
    )
    (net (code "132") (name "unconnected-(U9-PA4-Pad20)") (class "Default")
      (node (ref "U9") (pin "20") (pinfunction "PA4_20") (pintype "bidirectional"))
    )
    (net (code "133") (name "unconnected-(U9-PA8-Pad41)") (class "Default")
      (node (ref "U9") (pin "41") (pinfunction "PA8_41") (pintype "bidirectional"))
    )
    (net (code "134") (name "unconnected-(U9-PA9-Pad42)") (class "Default")
      (node (ref "U9") (pin "42") (pinfunction "PA9_42") (pintype "bidirectional"))
    )
    (net (code "135") (name "unconnected-(U9-PA10-Pad43)") (class "Default")
      (node (ref "U9") (pin "43") (pinfunction "PA10_43") (pintype "bidirectional"))
    )
    (net (code "136") (name "unconnected-(U9-PA11-Pad44)") (class "Default")
      (node (ref "U9") (pin "44") (pinfunction "PA11_44") (pintype "bidirectional"))
    )
    (net (code "137") (name "unconnected-(U9-PA12-Pad45)") (class "Default")
      (node (ref "U9") (pin "45") (pinfunction "PA12_45") (pintype "bidirectional"))
    )
    (net (code "138") (name "unconnected-(U9-PB0-Pad26)") (class "Default")
      (node (ref "U9") (pin "26") (pinfunction "PB0_26") (pintype "bidirectional"))
    )
    (net (code "139") (name "unconnected-(U9-PB1-Pad27)") (class "Default")
      (node (ref "U9") (pin "27") (pinfunction "PB1_27") (pintype "bidirectional"))
    )
    (net (code "140") (name "unconnected-(U9-PB1_2-Pad28)") (class "Default")
      (node (ref "U9") (pin "28") (pinfunction "PB1_2_28") (pintype "bidirectional"))
    )
    (net (code "141") (name "unconnected-(U9-PB6-Pad58)") (class "Default")
      (node (ref "U9") (pin "58") (pinfunction "PB6_58") (pintype "bidirectional"))
    )
    (net (code "142") (name "unconnected-(U9-PB8-Pad61)") (class "Default")
      (node (ref "U9") (pin "61") (pinfunction "PB8_61") (pintype "bidirectional"))
    )
    (net (code "143") (name "unconnected-(U9-PB9-Pad62)") (class "Default")
      (node (ref "U9") (pin "62") (pinfunction "PB9_62") (pintype "bidirectional"))
    )
    (net (code "144") (name "unconnected-(U9-PB10-Pad29)") (class "Default")
      (node (ref "U9") (pin "29") (pinfunction "PB10_29") (pintype "bidirectional"))
    )
    (net (code "145") (name "unconnected-(U9-PB11-Pad30)") (class "Default")
      (node (ref "U9") (pin "30") (pinfunction "PB11_30") (pintype "bidirectional"))
    )
    (net (code "146") (name "unconnected-(U9-PB12-Pad33)") (class "Default")
      (node (ref "U9") (pin "33") (pinfunction "PB12_33") (pintype "bidirectional"))
    )
    (net (code "147") (name "unconnected-(U9-PB13-Pad34)") (class "Default")
      (node (ref "U9") (pin "34") (pinfunction "PB13_34") (pintype "bidirectional"))
    )
    (net (code "148") (name "unconnected-(U9-PB14-Pad35)") (class "Default")
      (node (ref "U9") (pin "35") (pinfunction "PB14_35") (pintype "bidirectional"))
    )
    (net (code "149") (name "unconnected-(U9-PB15-Pad36)") (class "Default")
      (node (ref "U9") (pin "36") (pinfunction "PB15_36") (pintype "bidirectional"))
    )
    (net (code "150") (name "unconnected-(U9-PC4-Pad24)") (class "Default")
      (node (ref "U9") (pin "24") (pinfunction "PC4_24") (pintype "passive"))
    )
    (net (code "151") (name "unconnected-(U9-PC5-Pad25)") (class "Default")
      (node (ref "U9") (pin "25") (pinfunction "PC5_25") (pintype "bidirectional"))
    )
    (net (code "152") (name "unconnected-(U9-PC10-Pad51)") (class "Default")
      (node (ref "U9") (pin "51") (pinfunction "PC10_51") (pintype "bidirectional"))
    )
    (net (code "153") (name "unconnected-(U9-PC11-Pad52)") (class "Default")
      (node (ref "U9") (pin "52") (pinfunction "PC11_52") (pintype "bidirectional"))
    )
    (net (code "154") (name "unconnected-(U9-PC12-Pad53)") (class "Default")
      (node (ref "U9") (pin "53") (pinfunction "PC12_53") (pintype "bidirectional"))
    )
    (net (code "155") (name "unconnected-(U9-PC13-TAMPER-RTC-Pad2)") (class "Default")
      (node (ref "U9") (pin "2") (pinfunction "PC13-TAMPER-RTC_2") (pintype "input"))
    )
    (net (code "156") (name "unconnected-(U9-PC14-OSC32_IN-Pad3)") (class "Default")
      (node (ref "U9") (pin "3") (pinfunction "PC14-OSC32_IN_3") (pintype "input"))
    )
    (net (code "157") (name "unconnected-(U9-PC15-OSC32_OUT-Pad4)") (class "Default")
      (node (ref "U9") (pin "4") (pinfunction "PC15-OSC32_OUT_4") (pintype "output"))
    )
    (net (code "158") (name "unconnected-(U9-PD2-Pad54)") (class "Default")
      (node (ref "U9") (pin "54") (pinfunction "PD2_54") (pintype "bidirectional"))
    )
    (net (code "159") (name "unconnected-(Y2-EN-Pad1)") (class "Default")
      (node (ref "Y2") (pin "1") (pinfunction "EN_1") (pintype "bidirectional"))
    )
  )
)
